# design.net
KiCad netlist of a schematic drawn in Altium Designer
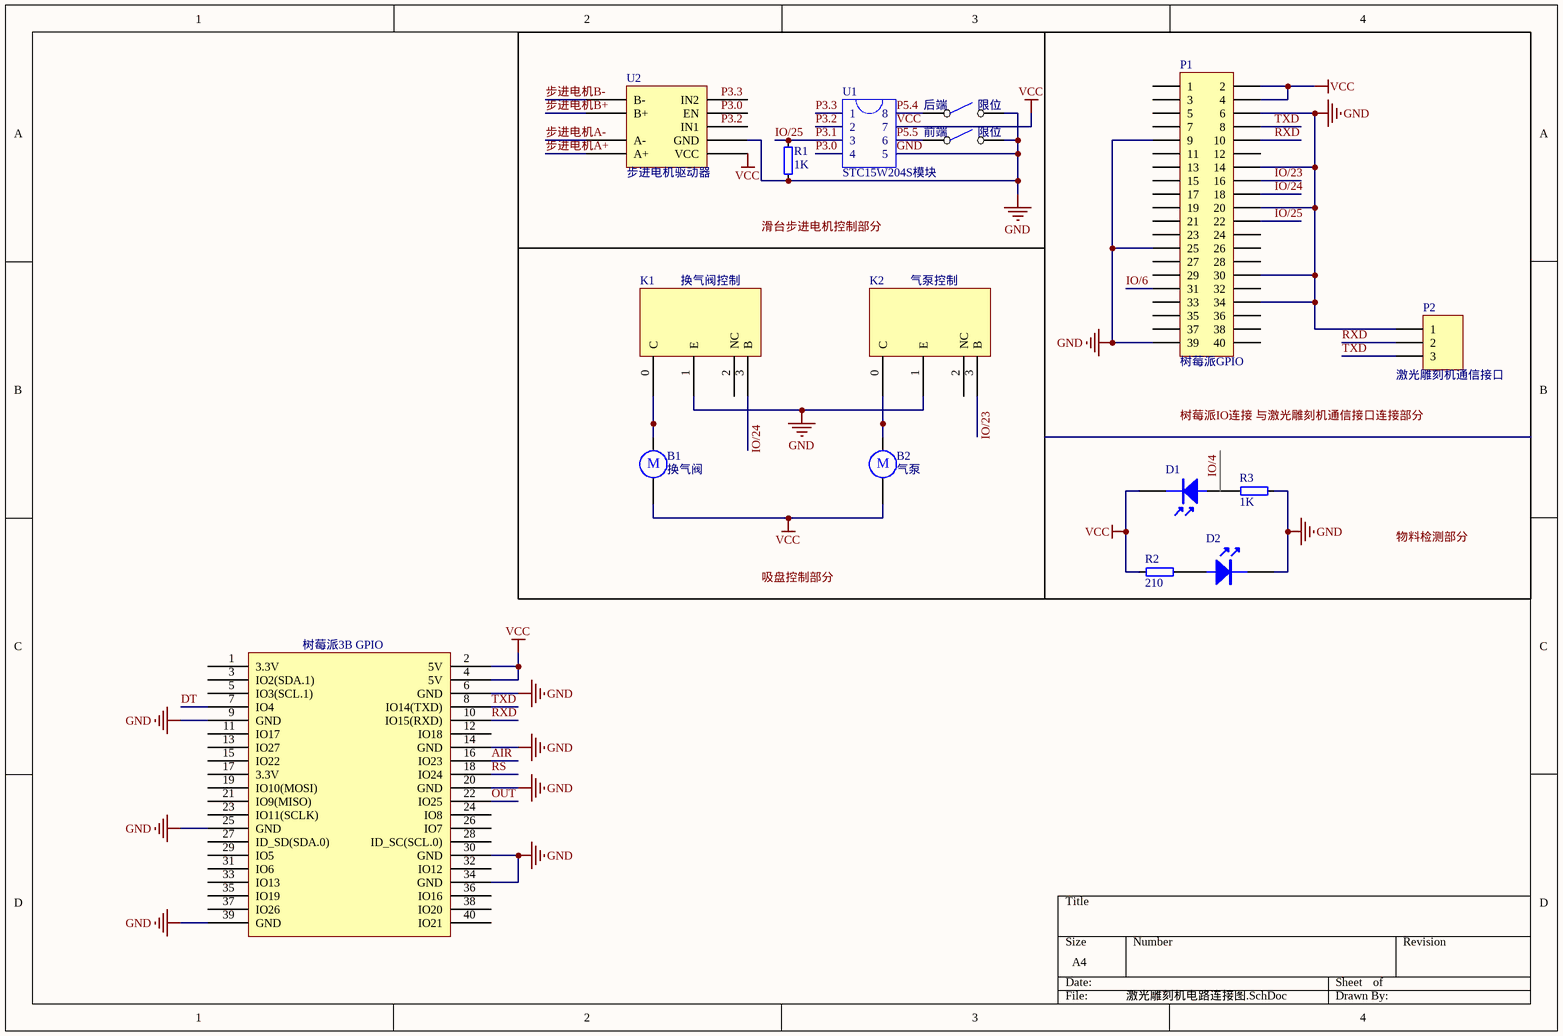
[diagram p0: 激光雕刻机电路连接图.SchDoc]

(export (version "E")
  (design (tool "Eeschema 10.0.6"))
  (components
    (comp (ref "*") (value "树莓派3B GPIO") (libsource (lib "Schlib1") (part "树莓派gpio")))
    (comp (ref "B1")
      (value "换气阀")
      (footprint "RB5-10.5")
      (description "Motor, General Kind")
      (fields (field (name "PUBLISHER") "Altium Limited"))
      (libsource (lib "Miscellaneous Devices") (part "Motor"))
    )
    (comp (ref "B2")
      (value "气泵")
      (footprint "RB5-10.5")
      (description "Motor, General Kind")
      (fields (field (name "PUBLISHER") "Altium Limited"))
      (libsource (lib "Miscellaneous Devices") (part "Motor"))
    )
    (comp (ref "D1") (value "~") (description "Photosensitive Diode") (libsource (lib "二极管") (part "光敏二极管")))
    (comp (ref "D2") (value "~") (footprint "DIODE0.4A") (libsource (lib "二极管") (part "发光二极管")))
    (comp (ref "K1") (value "换气阀控制") (libsource (lib "Schlib1") (part "固态继电器")))
    (comp (ref "K2") (value "气泵控制") (libsource (lib "Schlib1") (part "固态继电器")))
    (comp (ref "P1")
      (value "树莓派GPIO")
      (footprint "HDR2X20")
      (description "Header, 20-Pin, Dual row")
      (fields (field (name "PUBLISHER") "Altium Limited"))
      (libsource (lib "Miscellaneous Connectors") (part "Header 20X2"))
    )
    (comp (ref "P2")
      (value "激光雕刻机通信接口")
      (footprint "HDR1X3")
      (description "Header, 3-Pin")
      (fields (field (name "PUBLISHER") "Altium Limited"))
      (libsource (lib "Miscellaneous Connectors") (part "Header 3"))
    )
    (comp (ref "R1") (value "1K") (footprint "AXIAL0.3") (libsource (lib "电阻") (part "RES")))
    (comp (ref "R2") (value "210") (footprint "AXIAL0.3") (libsource (lib "电阻") (part "RES")))
    (comp (ref "R3") (value "1K") (footprint "AXIAL0.3") (libsource (lib "电阻") (part "RES")))
    (comp (ref "U1") (value "STC15W204S模块") (libsource (lib "常用元件库") (part "8PIN")))
    (comp (ref "U2") (value "步进电机驱动器") (libsource (lib "Schlib1") (part "步进电机驱动器")))
    (comp (ref "前端") (value "限位") (libsource (lib "开关") (part "单刀开关")))
    (comp (ref "后端") (value "限位") (libsource (lib "开关") (part "单刀开关")))
  )
  (nets
    (net (code "1") (name "/AIR") (class "Default")
      (node (ref "*") (pin "16") (pinfunction "IO23_16") (pintype "passive"))
    )
    (net (code "2") (name "/DT") (class "Default")
      (node (ref "*") (pin "7") (pinfunction "IO4_7") (pintype "passive"))
    )
    (net (code "4") (name "/IO{slash}6") (class "Default")
      (node (ref "P1") (pin "31") (pinfunction "31_31") (pintype "passive"))
    )
    (net (code "5") (name "/IO{slash}23") (class "Default")
      (node (ref "K2") (pin "3") (pinfunction "B_3") (pintype "passive"))
      (node (ref "P1") (pin "16") (pinfunction "16_16") (pintype "passive"))
    )
    (net (code "6") (name "/IO{slash}24") (class "Default")
      (node (ref "K1") (pin "3") (pinfunction "B_3") (pintype "passive"))
      (node (ref "P1") (pin "18") (pinfunction "18_18") (pintype "passive"))
    )
    (net (code "7") (name "/IO{slash}25") (class "Default")
      (node (ref "P1") (pin "22") (pinfunction "22_22") (pintype "passive"))
      (node (ref "R1") (pin "1") (pinfunction "1_1") (pintype "passive"))
      (node (ref "U1") (pin "3") (pinfunction "3_3") (pintype "passive"))
    )
    (net (code "8") (name "/OUT") (class "Default")
      (node (ref "*") (pin "22") (pinfunction "IO25_22") (pintype "passive"))
    )
    (net (code "9") (name "/P3.0") (class "Default")
      (node (ref "U1") (pin "4") (pinfunction "4_4") (pintype "passive"))
    )
    (net (code "10") (name "/P3.2") (class "Default")
      (node (ref "U1") (pin "2") (pinfunction "2_2") (pintype "passive"))
    )
    (net (code "11") (name "/P3.3") (class "Default")
      (node (ref "U1") (pin "1") (pinfunction "1_1") (pintype "passive"))
    )
    (net (code "14") (name "/RS") (class "Default")
      (node (ref "*") (pin "18") (pinfunction "IO24_18") (pintype "passive"))
    )
    (net (code "15") (name "/RXD") (class "Default")
      (node (ref "*") (pin "10") (pinfunction "IO15(RXD)_10") (pintype "passive"))
      (node (ref "P1") (pin "10") (pinfunction "10_10") (pintype "passive"))
      (node (ref "P2") (pin "2") (pinfunction "2_2") (pintype "passive"))
    )
    (net (code "16") (name "/TXD") (class "Default")
      (node (ref "*") (pin "8") (pinfunction "IO14(TXD)_8") (pintype "passive"))
      (node (ref "P1") (pin "8") (pinfunction "8_8") (pintype "passive"))
      (node (ref "P2") (pin "3") (pinfunction "3_3") (pintype "passive"))
    )
    (net (code "19") (name "/步进电机A+") (class "Default")
      (node (ref "U2") (pin "9") (pinfunction "A+_9") (pintype "passive"))
    )
    (net (code "20") (name "/步进电机A-") (class "Default")
      (node (ref "U2") (pin "10") (pinfunction "A-_10") (pintype "passive"))
    )
    (net (code "21") (name "/步进电机B+") (class "Default")
      (node (ref "U2") (pin "11") (pinfunction "B+_11") (pintype "passive"))
    )
    (net (code "22") (name "/步进电机B-") (class "Default")
      (node (ref "U2") (pin "12") (pinfunction "B-_12") (pintype "passive"))
    )
    (net (code "25") (name "GND") (class "Default")
      (node (ref "*") (pin "14") (pinfunction "GND_14") (pintype "passive"))
      (node (ref "*") (pin "20") (pinfunction "GND_20") (pintype "passive"))
      (node (ref "*") (pin "25") (pinfunction "GND_25") (pintype "passive"))
      (node (ref "*") (pin "30") (pinfunction "GND_30") (pintype "passive"))
      (node (ref "*") (pin "34") (pinfunction "GND_34") (pintype "passive"))
      (node (ref "*") (pin "39") (pinfunction "GND_39") (pintype "passive"))
      (node (ref "*") (pin "6") (pinfunction "GND_6") (pintype "passive"))
      (node (ref "*") (pin "9") (pinfunction "GND_9") (pintype "passive"))
      (node (ref "D2") (pin "K") (pinfunction "2_K") (pintype "passive"))
      (node (ref "K1") (pin "1") (pinfunction "E_1") (pintype "passive"))
      (node (ref "K2") (pin "1") (pinfunction "E_1") (pintype "passive"))
      (node (ref "P1") (pin "14") (pinfunction "14_14") (pintype "passive"))
      (node (ref "P1") (pin "20") (pinfunction "20_20") (pintype "passive"))
      (node (ref "P1") (pin "25") (pinfunction "25_25") (pintype "passive"))
      (node (ref "P1") (pin "30") (pinfunction "30_30") (pintype "passive"))
      (node (ref "P1") (pin "34") (pinfunction "34_34") (pintype "passive"))
      (node (ref "P1") (pin "39") (pinfunction "39_39") (pintype "passive"))
      (node (ref "P1") (pin "6") (pinfunction "6_6") (pintype "passive"))
      (node (ref "P1") (pin "9") (pinfunction "9_9") (pintype "passive"))
      (node (ref "P2") (pin "1") (pinfunction "1_1") (pintype "passive"))
      (node (ref "R1") (pin "2") (pinfunction "2_2") (pintype "passive"))
      (node (ref "R3") (pin "1") (pinfunction "1_1") (pintype "passive"))
      (node (ref "U1") (pin "5") (pinfunction "5_5") (pintype "passive"))
      (node (ref "U2") (pin "5") (pinfunction "GND_5") (pintype "passive"))
      (node (ref "前端") (pin "2") (pinfunction "2_2") (pintype "passive"))
      (node (ref "后端") (pin "2") (pinfunction "2_2") (pintype "passive"))
    )
    (net (code "26") (name "Net-(D1-A)") (class "Default")
      (node (ref "D1") (pin "1") (pinfunction "A_1") (pintype "passive"))
      (node (ref "R3") (pin "2") (pinfunction "2_2") (pintype "passive"))
    )
    (net (code "27") (name "Net-(D2-1)") (class "Default")
      (node (ref "D2") (pin "A") (pinfunction "1_A") (pintype "passive"))
      (node (ref "R2") (pin "1") (pinfunction "1_1") (pintype "passive"))
    )
    (net (code "28") (name "Net-(K1-C)") (class "Default")
      (node (ref "B1") (pin "1") (pinfunction "1_1") (pintype "passive"))
      (node (ref "K1") (pin "0") (pinfunction "C_0") (pintype "passive"))
    )
    (net (code "29") (name "Net-(K2-C)") (class "Default")
      (node (ref "B2") (pin "1") (pinfunction "1_1") (pintype "passive"))
      (node (ref "K2") (pin "0") (pinfunction "C_0") (pintype "passive"))
    )
    (net (code "30") (name "Net-(U1-Pad6)") (class "Default")
      (node (ref "U1") (pin "6") (pinfunction "6_6") (pintype "passive"))
      (node (ref "前端") (pin "1") (pinfunction "1_1") (pintype "passive"))
    )
    (net (code "31") (name "Net-(U1-Pad8)") (class "Default")
      (node (ref "U1") (pin "8") (pinfunction "8_8") (pintype "passive"))
      (node (ref "后端") (pin "1") (pinfunction "1_1") (pintype "passive"))
    )
    (net (code "32") (name "VCC") (class "Default")
      (node (ref "*") (pin "2") (pinfunction "5V_2") (pintype "passive"))
      (node (ref "*") (pin "4") (pinfunction "5V_4") (pintype "passive"))
      (node (ref "B1") (pin "2") (pinfunction "2_2") (pintype "passive"))
      (node (ref "B2") (pin "2") (pinfunction "2_2") (pintype "passive"))
      (node (ref "D1") (pin "2") (pinfunction "K_2") (pintype "passive"))
      (node (ref "P1") (pin "2") (pinfunction "2_2") (pintype "passive"))
      (node (ref "P1") (pin "4") (pinfunction "4_4") (pintype "passive"))
      (node (ref "R2") (pin "2") (pinfunction "2_2") (pintype "passive"))
      (node (ref "U1") (pin "7") (pinfunction "7_7") (pintype "passive"))
      (node (ref "U2") (pin "4") (pinfunction "VCC_4") (pintype "passive"))
    )
    (net (code "33") (name "unconnected-(*-3.3V-Pad1)") (class "Default")
      (node (ref "*") (pin "1") (pinfunction "3.3V_1") (pintype "passive"))
    )
    (net (code "34") (name "unconnected-(*-3.3V-Pad17)") (class "Default")
      (node (ref "*") (pin "17") (pinfunction "3.3V_17") (pintype "passive"))
    )
    (net (code "35") (name "unconnected-(*-ID_SC(SCL.0)-Pad28)") (class "Default")
      (node (ref "*") (pin "28") (pinfunction "ID_SC(SCL.0)_28") (pintype "passive"))
    )
    (net (code "36") (name "unconnected-(*-ID_SD(SDA.0)-Pad27)") (class "Default")
      (node (ref "*") (pin "27") (pinfunction "ID_SD(SDA.0)_27") (pintype "passive"))
    )
    (net (code "37") (name "unconnected-(*-IO2(SDA.1)-Pad3)") (class "Default")
      (node (ref "*") (pin "3") (pinfunction "IO2(SDA.1)_3") (pintype "passive"))
    )
    (net (code "38") (name "unconnected-(*-IO3(SCL.1)-Pad5)") (class "Default")
      (node (ref "*") (pin "5") (pinfunction "IO3(SCL.1)_5") (pintype "passive"))
    )
    (net (code "39") (name "unconnected-(*-IO5-Pad29)") (class "Default")
      (node (ref "*") (pin "29") (pinfunction "IO5_29") (pintype "passive"))
    )
    (net (code "40") (name "unconnected-(*-IO6-Pad31)") (class "Default")
      (node (ref "*") (pin "31") (pinfunction "IO6_31") (pintype "passive"))
    )
    (net (code "41") (name "unconnected-(*-IO7-Pad26)") (class "Default")
      (node (ref "*") (pin "26") (pinfunction "IO7_26") (pintype "passive"))
    )
    (net (code "42") (name "unconnected-(*-IO8-Pad24)") (class "Default")
      (node (ref "*") (pin "24") (pinfunction "IO8_24") (pintype "passive"))
    )
    (net (code "43") (name "unconnected-(*-IO9(MISO)-Pad21)") (class "Default")
      (node (ref "*") (pin "21") (pinfunction "IO9(MISO)_21") (pintype "passive"))
    )
    (net (code "44") (name "unconnected-(*-IO10(MOSI)-Pad19)") (class "Default")
      (node (ref "*") (pin "19") (pinfunction "IO10(MOSI)_19") (pintype "passive"))
    )
    (net (code "45") (name "unconnected-(*-IO11(SCLK)-Pad23)") (class "Default")
      (node (ref "*") (pin "23") (pinfunction "IO11(SCLK)_23") (pintype "passive"))
    )
    (net (code "46") (name "unconnected-(*-IO12-Pad32)") (class "Default")
      (node (ref "*") (pin "32") (pinfunction "IO12_32") (pintype "passive"))
    )
    (net (code "47") (name "unconnected-(*-IO13-Pad33)") (class "Default")
      (node (ref "*") (pin "33") (pinfunction "IO13_33") (pintype "passive"))
    )
    (net (code "48") (name "unconnected-(*-IO16-Pad36)") (class "Default")
      (node (ref "*") (pin "36") (pinfunction "IO16_36") (pintype "passive"))
    )
    (net (code "49") (name "unconnected-(*-IO17-Pad11)") (class "Default")
      (node (ref "*") (pin "11") (pinfunction "IO17_11") (pintype "passive"))
    )
    (net (code "50") (name "unconnected-(*-IO18-Pad12)") (class "Default")
      (node (ref "*") (pin "12") (pinfunction "IO18_12") (pintype "passive"))
    )
    (net (code "51") (name "unconnected-(*-IO19-Pad35)") (class "Default")
      (node (ref "*") (pin "35") (pinfunction "IO19_35") (pintype "passive"))
    )
    (net (code "52") (name "unconnected-(*-IO20-Pad38)") (class "Default")
      (node (ref "*") (pin "38") (pinfunction "IO20_38") (pintype "passive"))
    )
    (net (code "53") (name "unconnected-(*-IO21-Pad40)") (class "Default")
      (node (ref "*") (pin "40") (pinfunction "IO21_40") (pintype "passive"))
    )
    (net (code "54") (name "unconnected-(*-IO22-Pad15)") (class "Default")
      (node (ref "*") (pin "15") (pinfunction "IO22_15") (pintype "passive"))
    )
    (net (code "55") (name "unconnected-(*-IO26-Pad37)") (class "Default")
      (node (ref "*") (pin "37") (pinfunction "IO26_37") (pintype "passive"))
    )
    (net (code "56") (name "unconnected-(*-IO27-Pad13)") (class "Default")
      (node (ref "*") (pin "13") (pinfunction "IO27_13") (pintype "passive"))
    )
    (net (code "57") (name "unconnected-(K1-NC-Pad2)") (class "Default")
      (node (ref "K1") (pin "2") (pinfunction "NC_2") (pintype "passive"))
    )
    (net (code "58") (name "unconnected-(K2-NC-Pad2)") (class "Default")
      (node (ref "K2") (pin "2") (pinfunction "NC_2") (pintype "passive"))
    )
    (net (code "59") (name "unconnected-(P1-Pad1)") (class "Default")
      (node (ref "P1") (pin "1") (pinfunction "1_1") (pintype "passive"))
    )
    (net (code "60") (name "unconnected-(P1-Pad3)") (class "Default")
      (node (ref "P1") (pin "3") (pinfunction "3_3") (pintype "passive"))
    )
    (net (code "61") (name "unconnected-(P1-Pad5)") (class "Default")
      (node (ref "P1") (pin "5") (pinfunction "5_5") (pintype "passive"))
    )
    (net (code "62") (name "unconnected-(P1-Pad7)") (class "Default")
      (node (ref "P1") (pin "7") (pinfunction "7_7") (pintype "passive"))
    )
    (net (code "63") (name "unconnected-(P1-Pad11)") (class "Default")
      (node (ref "P1") (pin "11") (pinfunction "11_11") (pintype "passive"))
    )
    (net (code "64") (name "unconnected-(P1-Pad12)") (class "Default")
      (node (ref "P1") (pin "12") (pinfunction "12_12") (pintype "passive"))
    )
    (net (code "65") (name "unconnected-(P1-Pad13)") (class "Default")
      (node (ref "P1") (pin "13") (pinfunction "13_13") (pintype "passive"))
    )
    (net (code "66") (name "unconnected-(P1-Pad15)") (class "Default")
      (node (ref "P1") (pin "15") (pinfunction "15_15") (pintype "passive"))
    )
    (net (code "67") (name "unconnected-(P1-Pad17)") (class "Default")
      (node (ref "P1") (pin "17") (pinfunction "17_17") (pintype "passive"))
    )
    (net (code "68") (name "unconnected-(P1-Pad19)") (class "Default")
      (node (ref "P1") (pin "19") (pinfunction "19_19") (pintype "passive"))
    )
    (net (code "69") (name "unconnected-(P1-Pad21)") (class "Default")
      (node (ref "P1") (pin "21") (pinfunction "21_21") (pintype "passive"))
    )
    (net (code "70") (name "unconnected-(P1-Pad23)") (class "Default")
      (node (ref "P1") (pin "23") (pinfunction "23_23") (pintype "passive"))
    )
    (net (code "71") (name "unconnected-(P1-Pad24)") (class "Default")
      (node (ref "P1") (pin "24") (pinfunction "24_24") (pintype "passive"))
    )
    (net (code "72") (name "unconnected-(P1-Pad26)") (class "Default")
      (node (ref "P1") (pin "26") (pinfunction "26_26") (pintype "passive"))
    )
    (net (code "73") (name "unconnected-(P1-Pad27)") (class "Default")
      (node (ref "P1") (pin "27") (pinfunction "27_27") (pintype "passive"))
    )
    (net (code "74") (name "unconnected-(P1-Pad28)") (class "Default")
      (node (ref "P1") (pin "28") (pinfunction "28_28") (pintype "passive"))
    )
    (net (code "75") (name "unconnected-(P1-Pad29)") (class "Default")
      (node (ref "P1") (pin "29") (pinfunction "29_29") (pintype "passive"))
    )
    (net (code "76") (name "unconnected-(P1-Pad32)") (class "Default")
      (node (ref "P1") (pin "32") (pinfunction "32_32") (pintype "passive"))
    )
    (net (code "77") (name "unconnected-(P1-Pad33)") (class "Default")
      (node (ref "P1") (pin "33") (pinfunction "33_33") (pintype "passive"))
    )
    (net (code "78") (name "unconnected-(P1-Pad35)") (class "Default")
      (node (ref "P1") (pin "35") (pinfunction "35_35") (pintype "passive"))
    )
    (net (code "79") (name "unconnected-(P1-Pad36)") (class "Default")
      (node (ref "P1") (pin "36") (pinfunction "36_36") (pintype "passive"))
    )
    (net (code "80") (name "unconnected-(P1-Pad37)") (class "Default")
      (node (ref "P1") (pin "37") (pinfunction "37_37") (pintype "passive"))
    )
    (net (code "81") (name "unconnected-(P1-Pad38)") (class "Default")
      (node (ref "P1") (pin "38") (pinfunction "38_38") (pintype "passive"))
    )
    (net (code "82") (name "unconnected-(P1-Pad40)") (class "Default")
      (node (ref "P1") (pin "40") (pinfunction "40_40") (pintype "passive"))
    )
    (net (code "83") (name "unconnected-(U2-EN-Pad7)") (class "Default")
      (node (ref "U2") (pin "7") (pinfunction "EN_7") (pintype "passive"))
    )
    (net (code "84") (name "unconnected-(U2-IN1-Pad6)") (class "Default")
      (node (ref "U2") (pin "6") (pinfunction "IN1_6") (pintype "passive"))
    )
    (net (code "85") (name "unconnected-(U2-IN2-Pad8)") (class "Default")
      (node (ref "U2") (pin "8") (pinfunction "IN2_8") (pintype "passive"))
    )
  )
)
